# ESC_Header.net
KiCad netlist of a schematic drawn in Altium Designer
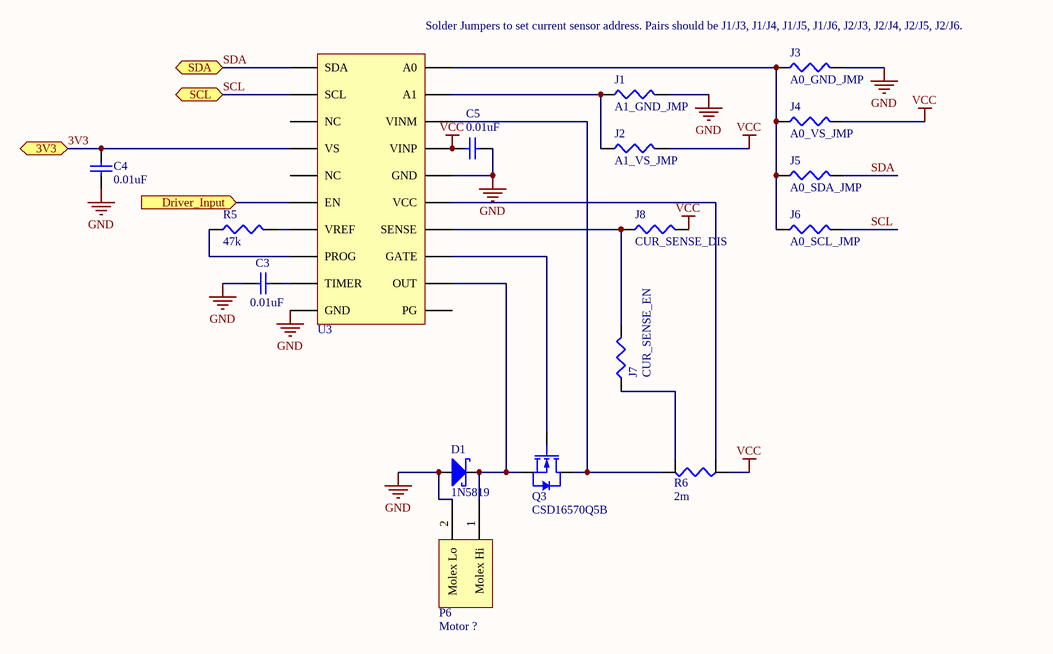
[diagram p0: ESC_Header.SchDoc]

(export (version "E")
  (design (tool "Eeschema 10.0.6"))
  (components
    (comp (ref "C3")
      (value "0.01uF")
      (footprint "C1206")
      (description "Capacitor (Semiconductor SIM Model)")
      (fields (field (name "Comment") "Cap Semi") (field (name "PUBLISHER") "Altium Limited"))
      (libsource (lib "Miscellaneous Devices") (part "Cap Semi"))
    )
    (comp (ref "C4")
      (value "0.01uF")
      (footprint "C1206")
      (description "Capacitor (Semiconductor SIM Model)")
      (fields (field (name "Comment") "Cap Semi") (field (name "PUBLISHER") "Altium Limited"))
      (libsource (lib "Miscellaneous Devices") (part "Cap Semi"))
    )
    (comp (ref "C5")
      (value "0.01uF")
      (footprint "C1206")
      (description "Capacitor (Semiconductor SIM Model)")
      (fields (field (name "Comment") "Cap Semi") (field (name "PUBLISHER") "Altium Limited"))
      (libsource (lib "Miscellaneous Devices") (part "Cap Semi"))
    )
    (comp (ref "D1")
      (value "1N5819")
      (footprint "1N58xx")
      (description "1A Schottky Barrier Rectifier Diode")
      (libsource (lib "Merge_ESC_Board_Library") (part "1N58xx"))
    )
    (comp (ref "J1")
      (value "A1_GND_JMP")
      (footprint "J1-0603")
      (description "Resistor")
      (fields (field (name "PUBLISHER") "Altium Limited"))
      (libsource (lib "Miscellaneous Devices") (part "Res3"))
    )
    (comp (ref "J2")
      (value "A1_VS_JMP")
      (footprint "J1-0603")
      (description "Resistor")
      (fields (field (name "PUBLISHER") "Altium Limited"))
      (libsource (lib "Miscellaneous Devices") (part "Res3"))
    )
    (comp (ref "J3")
      (value "A0_GND_JMP")
      (footprint "J1-0603")
      (description "Resistor")
      (fields (field (name "PUBLISHER") "Altium Limited"))
      (libsource (lib "Miscellaneous Devices") (part "Res3"))
    )
    (comp (ref "J4")
      (value "A0_VS_JMP")
      (footprint "J1-0603")
      (description "Resistor")
      (fields (field (name "PUBLISHER") "Altium Limited"))
      (libsource (lib "Miscellaneous Devices") (part "Res3"))
    )
    (comp (ref "J5")
      (value "A0_SDA_JMP")
      (footprint "J1-0603")
      (description "Resistor")
      (fields (field (name "PUBLISHER") "Altium Limited"))
      (libsource (lib "Miscellaneous Devices") (part "Res3"))
    )
    (comp (ref "J6")
      (value "A0_SCL_JMP")
      (footprint "J1-0603")
      (description "Resistor")
      (fields (field (name "PUBLISHER") "Altium Limited"))
      (libsource (lib "Miscellaneous Devices") (part "Res3"))
    )
    (comp (ref "J7")
      (value "CUR_SENSE_EN")
      (footprint "J1-0603")
      (description "Resistor")
      (fields (field (name "PUBLISHER") "Altium Limited"))
      (libsource (lib "Miscellaneous Devices") (part "Res3"))
    )
    (comp (ref "J8")
      (value "CUR_SENSE_DIS")
      (footprint "J1-0603")
      (description "Resistor")
      (fields (field (name "PUBLISHER") "Altium Limited"))
      (libsource (lib "Miscellaneous Devices") (part "Res3"))
    )
    (comp (ref "P6")
      (value "Motor ?")
      (footprint "76829-0102")
      (fields (field (name "MFGR_PART_NUM") "76829-0102"))
      (libsource (lib "Merge_ESC_Board_Library") (part "Megafit Slim Vert 2 Peg"))
    )
    (comp (ref "Q3")
      (value "CSD16570Q5B")
      (footprint "CSD16570Q5B")
      (description "MOSFET N-CH 25V 100A 8VSON")
      (fields (field (name "MANUFACTURER") "Texas Instruments"))
      (libsource (lib "Merge_ESC_Board_Library") (part "CSD16570Q5B"))
    )
    (comp (ref "R5")
      (value "47k")
      (footprint "J1-0603")
      (description "Resistor")
      (fields (field (name "PUBLISHER") "Altium Limited"))
      (libsource (lib "Miscellaneous Devices") (part "Res3"))
    )
    (comp (ref "R6")
      (value "2m")
      (footprint "WSL27262L000FEB")
      (libsource (lib "Merge_ESC_Board_Library") (part "WSL27262L000FEB"))
    )
    (comp (ref "U3")
      (value "TPS2481")
      (footprint "TPS2481")
      (description "Positive voltage, intelligent protection device/hotswap controller and I2C current monitor")
      (libsource (lib "Merge_ESC_Board_Library") (part "TPS2481"))
    )
  )
  (nets
    (net (code "1") (name "/3V3") (class "Default")
      (node (ref "C4") (pin "2") (pinfunction "2_2") (pintype "passive"))
      (node (ref "U3") (pin "4") (pinfunction "VS_4") (pintype "passive"))
    )
    (net (code "2") (name "/Driver_Input") (class "Default")
      (node (ref "U3") (pin "6") (pinfunction "EN_6") (pintype "passive"))
    )
    (net (code "3") (name "/SCL") (class "Default")
      (node (ref "J6") (pin "2") (pinfunction "2_2") (pintype "passive"))
      (node (ref "U3") (pin "2") (pinfunction "SCL_2") (pintype "passive"))
    )
    (net (code "4") (name "/SDA") (class "Default")
      (node (ref "J5") (pin "2") (pinfunction "2_2") (pintype "passive"))
      (node (ref "U3") (pin "1") (pinfunction "SDA_1") (pintype "passive"))
    )
    (net (code "5") (name "GND") (class "Default")
      (node (ref "C3") (pin "1") (pinfunction "1_1") (pintype "passive"))
      (node (ref "C4") (pin "1") (pinfunction "1_1") (pintype "passive"))
      (node (ref "C5") (pin "1") (pinfunction "1_1") (pintype "passive"))
      (node (ref "D1") (pin "A") (pinfunction "Anode_A") (pintype "passive"))
      (node (ref "J1") (pin "2") (pinfunction "2_2") (pintype "passive"))
      (node (ref "J3") (pin "2") (pinfunction "2_2") (pintype "passive"))
      (node (ref "P6") (pin "2") (pinfunction "Molex_Lo_2") (pintype "passive"))
      (node (ref "U3") (pin "10") (pinfunction "GND_10") (pintype "passive"))
      (node (ref "U3") (pin "16") (pinfunction "GND_16") (pintype "passive"))
    )
    (net (code "6") (name "Net-(D1-Cathode)") (class "Default")
      (node (ref "D1") (pin "K") (pinfunction "Cathode_K") (pintype "passive"))
      (node (ref "P6") (pin "1") (pinfunction "Molex_Hi_1") (pintype "passive"))
      (node (ref "Q3") (pin "S") (pinfunction "Source_S") (pintype "passive"))
      (node (ref "U3") (pin "12") (pinfunction "OUT_12") (pintype "passive"))
    )
    (net (code "7") (name "Net-(Q3-Drain)") (class "Default")
      (node (ref "Q3") (pin "D") (pinfunction "Drain_D") (pintype "passive"))
      (node (ref "R6") (pin "2") (pinfunction "1_2") (pintype "passive"))
      (node (ref "U3") (pin "18") (pinfunction "VINM_18") (pintype "passive"))
    )
    (net (code "8") (name "Net-(Q3-Gate)") (class "Default")
      (node (ref "Q3") (pin "G") (pinfunction "Gate_G") (pintype "passive"))
      (node (ref "U3") (pin "13") (pinfunction "GATE_13") (pintype "passive"))
    )
    (net (code "9") (name "Net-(R6-3)") (class "Default")
      (node (ref "J7") (pin "1") (pinfunction "1_1") (pintype "passive"))
      (node (ref "R6") (pin "4") (pinfunction "3_4") (pintype "passive"))
    )
    (net (code "10") (name "Net-(R6-4)") (class "Default")
      (node (ref "R6") (pin "3") (pinfunction "4_3") (pintype "passive"))
      (node (ref "U3") (pin "15") (pinfunction "VCC_15") (pintype "passive"))
    )
    (net (code "11") (name "Net-(U3-A0)") (class "Default")
      (node (ref "J3") (pin "1") (pinfunction "1_1") (pintype "passive"))
      (node (ref "J4") (pin "1") (pinfunction "1_1") (pintype "passive"))
      (node (ref "J5") (pin "1") (pinfunction "1_1") (pintype "passive"))
      (node (ref "J6") (pin "1") (pinfunction "1_1") (pintype "passive"))
      (node (ref "U3") (pin "20") (pinfunction "A0_20") (pintype "passive"))
    )
    (net (code "12") (name "Net-(U3-A1)") (class "Default")
      (node (ref "J1") (pin "1") (pinfunction "1_1") (pintype "passive"))
      (node (ref "J2") (pin "1") (pinfunction "1_1") (pintype "passive"))
      (node (ref "U3") (pin "19") (pinfunction "A1_19") (pintype "passive"))
    )
    (net (code "13") (name "Net-(U3-PROG)") (class "Default")
      (node (ref "R5") (pin "1") (pinfunction "1_1") (pintype "passive"))
      (node (ref "U3") (pin "8") (pinfunction "PROG_8") (pintype "passive"))
    )
    (net (code "14") (name "Net-(U3-SENSE)") (class "Default")
      (node (ref "J7") (pin "2") (pinfunction "2_2") (pintype "passive"))
      (node (ref "J8") (pin "1") (pinfunction "1_1") (pintype "passive"))
      (node (ref "U3") (pin "14") (pinfunction "SENSE_14") (pintype "passive"))
    )
    (net (code "15") (name "Net-(U3-TIMER)") (class "Default")
      (node (ref "C3") (pin "2") (pinfunction "2_2") (pintype "passive"))
      (node (ref "U3") (pin "9") (pinfunction "TIMER_9") (pintype "passive"))
    )
    (net (code "16") (name "Net-(U3-VREF)") (class "Default")
      (node (ref "R5") (pin "2") (pinfunction "2_2") (pintype "passive"))
      (node (ref "U3") (pin "7") (pinfunction "VREF_7") (pintype "passive"))
    )
    (net (code "17") (name "VCC") (class "Default")
      (node (ref "C5") (pin "2") (pinfunction "2_2") (pintype "passive"))
      (node (ref "J2") (pin "2") (pinfunction "2_2") (pintype "passive"))
      (node (ref "J4") (pin "2") (pinfunction "2_2") (pintype "passive"))
      (node (ref "J8") (pin "2") (pinfunction "2_2") (pintype "passive"))
      (node (ref "R6") (pin "1") (pinfunction "2_1") (pintype "passive"))
      (node (ref "U3") (pin "17") (pinfunction "VINP_17") (pintype "passive"))
    )
    (net (code "18") (name "unconnected-(U3-NC-Pad3)") (class "Default")
      (node (ref "U3") (pin "3") (pinfunction "NC_3") (pintype "passive"))
    )
    (net (code "19") (name "unconnected-(U3-NC-Pad5)") (class "Default")
      (node (ref "U3") (pin "5") (pinfunction "NC_5") (pintype "passive"))
    )
    (net (code "20") (name "unconnected-(U3-PG-Pad11)") (class "Default")
      (node (ref "U3") (pin "11") (pinfunction "PG_11") (pintype "passive"))
    )
  )
)
